# hid.net
KiCad netlist of a schematic drawn in Altium Designer
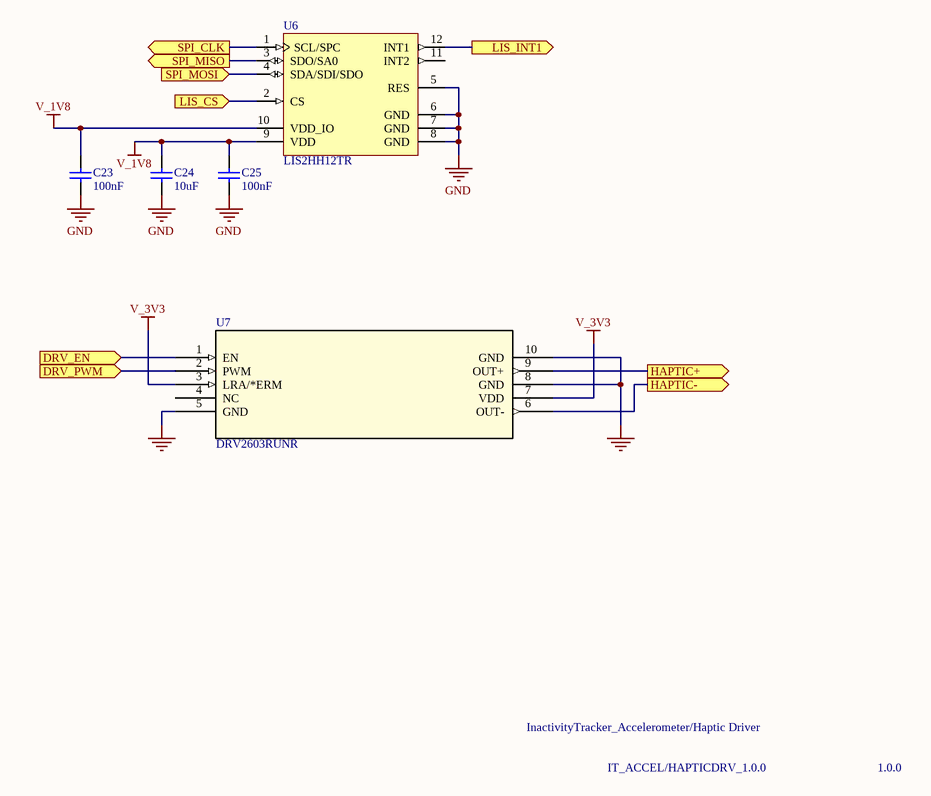
[diagram p0: hid.SchDoc]

(export (version "E")
  (design (tool "Eeschema 10.0.6"))
  (components
    (comp (ref "C23")
      (value "100nF")
      (footprint "CAPC1005X55X25NL05T10")
      (fields (field (name "PART NUMBER") "GRM155R71H104KE14D") (field (name "MANUFACTURER") "Murata"))
      (libsource (lib "Altium Content Vault") (part "CAP"))
    )
    (comp (ref "C24")
      (value "10uF")
      (footprint "CAPC1005X55X25NL05T10")
      (fields (field (name "PART NUMBER") "GRM155R61A105KE15D") (field (name "MANUFACTURER") "Murata"))
      (libsource (lib "Altium Content Vault") (part "CAP"))
    )
    (comp (ref "C25")
      (value "100nF")
      (footprint "CAPC1005X55X25NL05T10")
      (fields (field (name "PART NUMBER") "GRM155R71H104KE14D") (field (name "MANUFACTURER") "Murata"))
      (libsource (lib "Altium Content Vault") (part "CAP"))
    )
    (comp (ref "U6")
      (value "LIS2HH12TR")
      (footprint "STM-LGA-12")
      (fields (field (name "MANUFACTURER") "STMicroelectronics"))
      (libsource (lib "Altium Content Vault") (part "STM-LIS2HH12-LGA-12"))
    )
    (comp (ref "U7")
      (value "DRV2603RUNR")
      (footprint "RUN10")
      (description "Motor Driver Power MOSFET Parallel, PWM 10-QFN (2x2)")
      (fields (field (name "COPYRIGHT") "Copyright (C) 2018 Accelerated Designs. All rights reserved"))
      (libsource (lib "TIMicrocontrollers") (part "DRV2603RUNR"))
    )
  )
  (nets
    (net (code "1") (name "/DRV_EN") (class "Default")
      (node (ref "U7") (pin "1") (pinfunction "EN_1") (pintype "input"))
    )
    (net (code "2") (name "/DRV_PWM") (class "Default")
      (node (ref "U7") (pin "2") (pinfunction "PWM_2") (pintype "input"))
    )
    (net (code "3") (name "/HAPTIC+") (class "Default")
      (node (ref "U7") (pin "9") (pinfunction "OUT+_9") (pintype "output"))
    )
    (net (code "4") (name "/HAPTIC-") (class "Default")
      (node (ref "U7") (pin "6") (pinfunction "OUT-_6") (pintype "output"))
    )
    (net (code "5") (name "/LIS_CS") (class "Default")
      (node (ref "U6") (pin "2") (pinfunction "CS_2") (pintype "input"))
    )
    (net (code "6") (name "/LIS_INT1") (class "Default")
      (node (ref "U6") (pin "12") (pinfunction "INT1_12") (pintype "output"))
    )
    (net (code "7") (name "/SPI_CLK") (class "Default")
      (node (ref "U6") (pin "1") (pinfunction "SCL/SPC_1") (pintype "input"))
    )
    (net (code "8") (name "/SPI_MISO") (class "Default")
      (node (ref "U6") (pin "3") (pinfunction "SDO/SA0_3") (pintype "bidirectional"))
    )
    (net (code "9") (name "/SPI_MOSI") (class "Default")
      (node (ref "U6") (pin "4") (pinfunction "SDA/SDI/SDO_4") (pintype "bidirectional"))
    )
    (net (code "10") (name "GND") (class "Default")
      (node (ref "C23") (pin "1") (pinfunction "1_1") (pintype "passive"))
      (node (ref "C24") (pin "2") (pinfunction "2_2") (pintype "passive"))
      (node (ref "C25") (pin "1") (pinfunction "1_1") (pintype "passive"))
      (node (ref "U6") (pin "5") (pinfunction "RES_5") (pintype "passive"))
      (node (ref "U6") (pin "6") (pinfunction "GND_6") (pintype "power_in"))
      (node (ref "U6") (pin "7") (pinfunction "GND_7") (pintype "power_in"))
      (node (ref "U6") (pin "8") (pinfunction "GND_8") (pintype "power_in"))
      (node (ref "U7") (pin "10") (pinfunction "GND_10") (pintype "power_in"))
      (node (ref "U7") (pin "5") (pinfunction "GND_5") (pintype "power_in"))
      (node (ref "U7") (pin "8") (pinfunction "GND_8") (pintype "power_in"))
    )
    (net (code "11") (name "V_1V8") (class "Default")
      (node (ref "C23") (pin "2") (pinfunction "2_2") (pintype "passive"))
      (node (ref "C24") (pin "1") (pinfunction "1_1") (pintype "passive"))
      (node (ref "C25") (pin "2") (pinfunction "2_2") (pintype "passive"))
      (node (ref "U6") (pin "10") (pinfunction "VDD_IO_10") (pintype "power_in"))
      (node (ref "U6") (pin "9") (pinfunction "VDD_9") (pintype "power_in"))
    )
    (net (code "12") (name "V_3V3") (class "Default")
      (node (ref "U7") (pin "3") (pinfunction "LRA/*ERM_3") (pintype "input"))
      (node (ref "U7") (pin "7") (pinfunction "VDD_7") (pintype "power_in"))
    )
    (net (code "13") (name "unconnected-(U6-INT2-Pad11)") (class "Default")
      (node (ref "U6") (pin "11") (pinfunction "INT2_11") (pintype "output"))
    )
    (net (code "14") (name "unconnected-(U7-NC-Pad4)") (class "Default")
      (node (ref "U7") (pin "4") (pinfunction "NC_4") (pintype "passive"))
    )
  )
)
